# OsciloscopioVers_oFinal.net
KiCad netlist of a schematic drawn in EAGLE
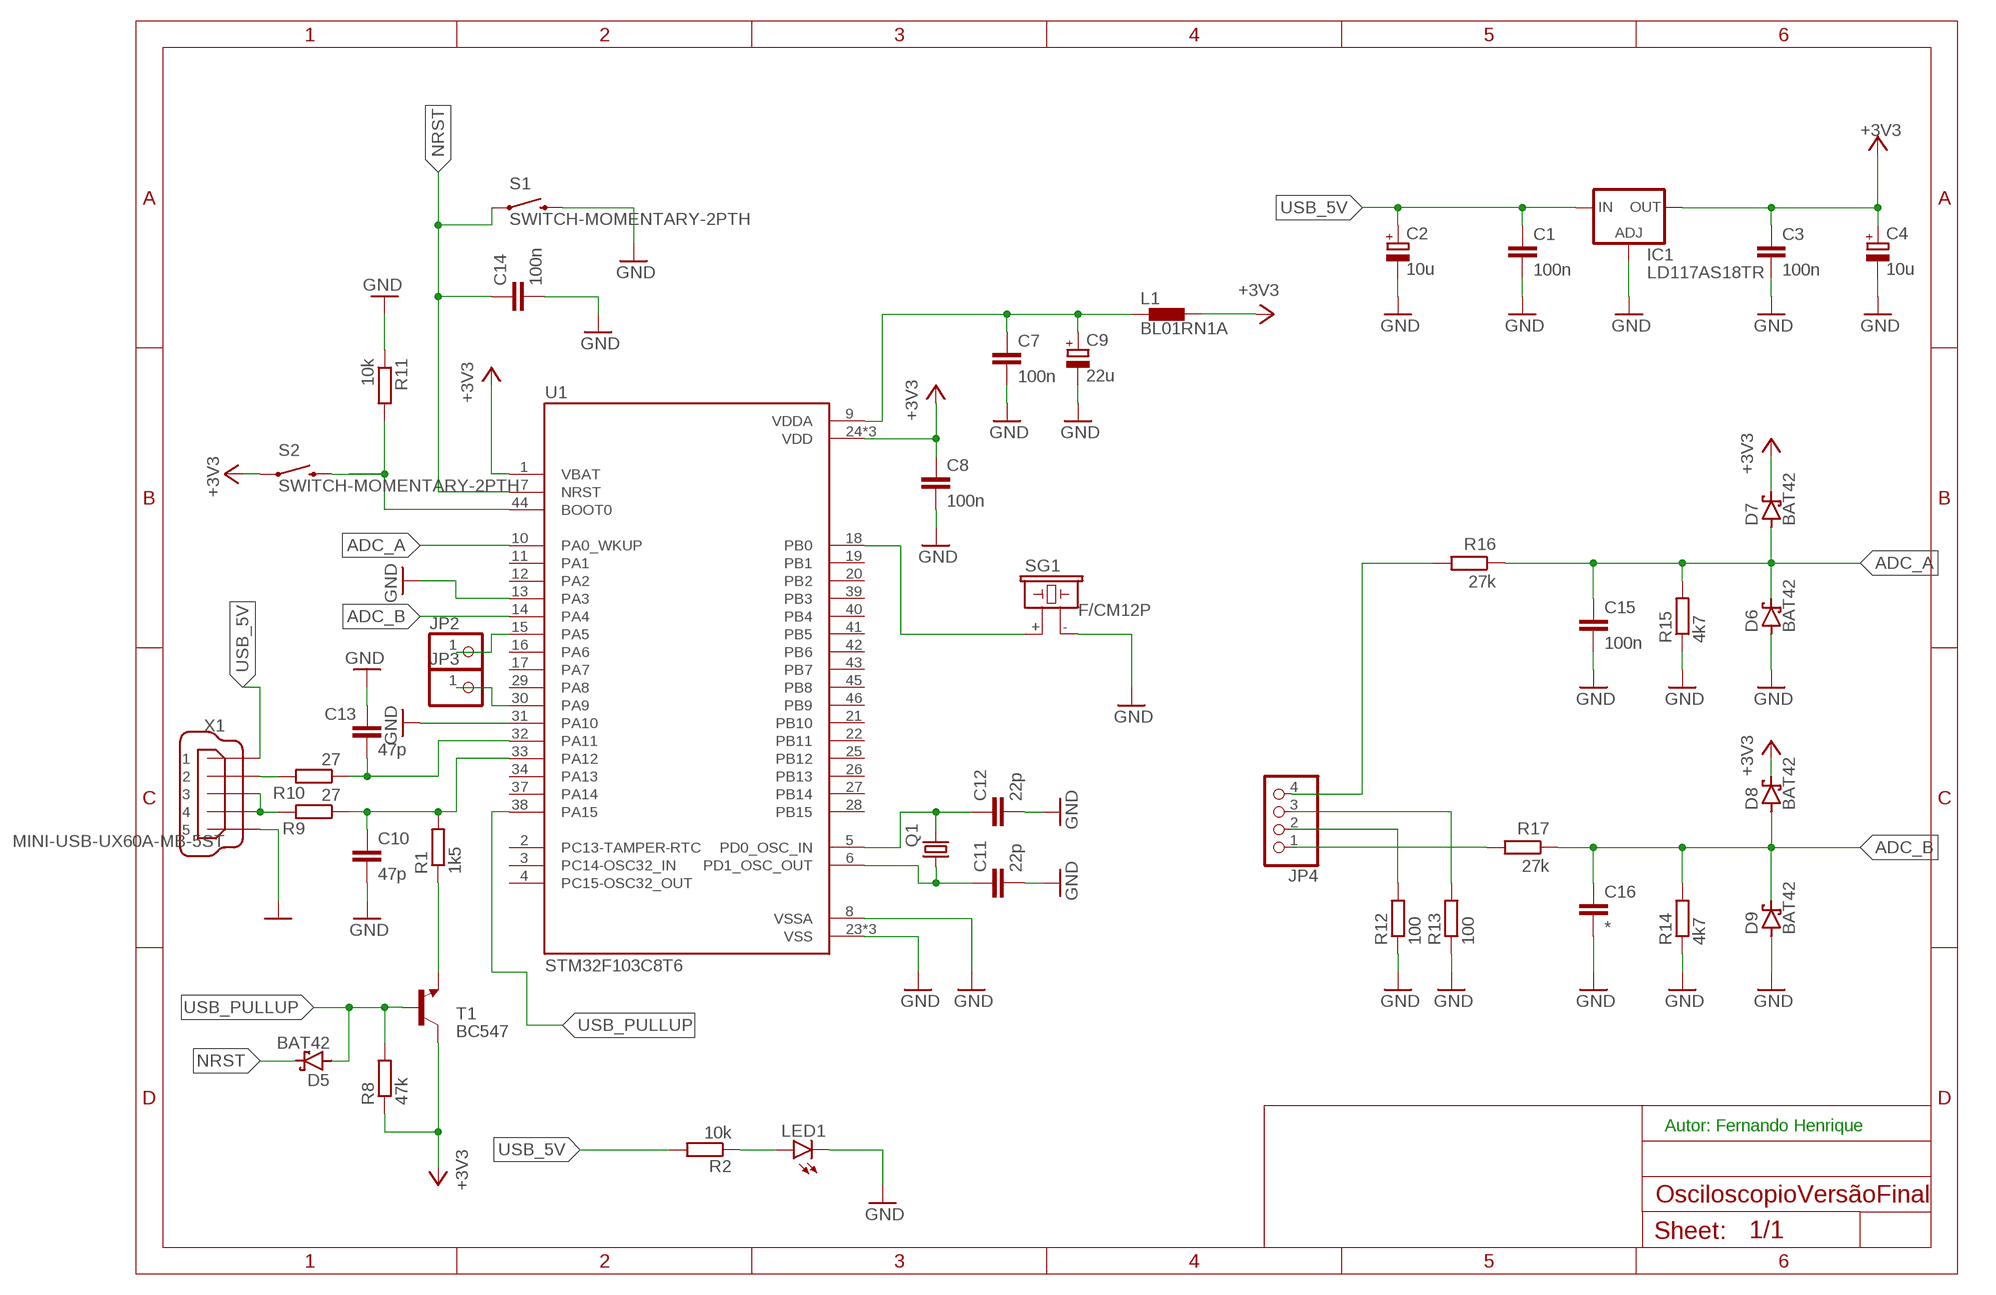
[diagram p0: schematic, sheet 1]

(export (version "E")
  (design (tool "Eeschema 10.0.6"))
  (components
    (comp (ref "C1")
      (value "100n")
      (footprint "eagle-import:C1206")
      (libsource (lib "eagle-import") (part "C-EUC1206"))
    )
    (comp (ref "C2")
      (value "10u")
      (footprint "eagle-import:B45181B")
      (libsource (lib "eagle-import") (part "CPOL-EUB45181B"))
    )
    (comp (ref "C3")
      (value "100n")
      (footprint "eagle-import:C1206")
      (libsource (lib "eagle-import") (part "C-EUC1206"))
    )
    (comp (ref "C4")
      (value "10u")
      (footprint "eagle-import:B45181B")
      (libsource (lib "eagle-import") (part "CPOL-EUB45181B"))
    )
    (comp (ref "C7")
      (value "100n")
      (footprint "eagle-import:C1206")
      (libsource (lib "eagle-import") (part "C-EUC1206"))
    )
    (comp (ref "C8")
      (value "100n")
      (footprint "eagle-import:C1206")
      (libsource (lib "eagle-import") (part "C-EUC1206"))
    )
    (comp (ref "C9")
      (value "22u")
      (footprint "eagle-import:B45181B")
      (libsource (lib "eagle-import") (part "CPOL-EUB45181B"))
    )
    (comp (ref "C10")
      (value "47p")
      (footprint "eagle-import:C1206")
      (libsource (lib "eagle-import") (part "C-EUC1206"))
    )
    (comp (ref "C11")
      (value "22p")
      (footprint "eagle-import:C1206")
      (libsource (lib "eagle-import") (part "C-EUC1206"))
    )
    (comp (ref "C12")
      (value "22p")
      (footprint "eagle-import:C1206")
      (libsource (lib "eagle-import") (part "C-EUC1206"))
    )
    (comp (ref "C13")
      (value "47p")
      (footprint "eagle-import:C1206")
      (libsource (lib "eagle-import") (part "C-EUC1206"))
    )
    (comp (ref "C14")
      (value "100n")
      (footprint "eagle-import:C1206")
      (libsource (lib "eagle-import") (part "C-EUC1206"))
    )
    (comp (ref "C15")
      (value "100n")
      (footprint "eagle-import:C1206")
      (libsource (lib "eagle-import") (part "C-EUC1206"))
    )
    (comp (ref "C16")
      (value "*")
      (footprint "eagle-import:C1206")
      (libsource (lib "eagle-import") (part "C-EUC1206"))
    )
    (comp (ref "D5")
      (value "BAT42")
      (footprint "eagle-import:DO35-10")
      (libsource (lib "eagle-import") (part "BAT42"))
    )
    (comp (ref "D6")
      (value "BAT42")
      (footprint "eagle-import:DO35-10")
      (libsource (lib "eagle-import") (part "BAT42"))
    )
    (comp (ref "D7")
      (value "BAT42")
      (footprint "eagle-import:DO35-10")
      (libsource (lib "eagle-import") (part "BAT42"))
    )
    (comp (ref "D8")
      (value "BAT42")
      (footprint "eagle-import:DO35-10")
      (libsource (lib "eagle-import") (part "BAT42"))
    )
    (comp (ref "D9")
      (value "BAT42")
      (footprint "eagle-import:DO35-10")
      (libsource (lib "eagle-import") (part "BAT42"))
    )
    (comp (ref "IC1")
      (value "LD117AS18TR")
      (footprint "eagle-import:SOT223")
      (libsource (lib "eagle-import") (part "LD117A?S18TR"))
    )
    (comp (ref "JP2")
      (value "PINHD-1X1")
      (footprint "eagle-import:1X01")
      (libsource (lib "eagle-import") (part "PINHD-1X1"))
    )
    (comp (ref "JP3")
      (value "PINHD-1X1")
      (footprint "eagle-import:1X01")
      (libsource (lib "eagle-import") (part "PINHD-1X1"))
    )
    (comp (ref "JP4")
      (value "PINHD-1X4")
      (footprint "eagle-import:1X04")
      (libsource (lib "eagle-import") (part "PINHD-1X4"))
    )
    (comp (ref "L1")
      (value "BL01RN1A")
      (footprint "eagle-import:BL01RN1A")
      (libsource (lib "eagle-import") (part "BL01RN1A"))
    )
    (comp (ref "LED1")
      (value "LED3MM")
      (footprint "eagle-import:LED3MM")
      (libsource (lib "eagle-import") (part "LED3MM"))
    )
    (comp (ref "Q1")
      (value "CRYSTALHC49U-V")
      (footprint "eagle-import:HC49U-V")
      (libsource (lib "eagle-import") (part "CRYSTALHC49U-V"))
    )
    (comp (ref "R1")
      (value "1k5")
      (footprint "eagle-import:R1206")
      (libsource (lib "eagle-import") (part "R-EU_R1206"))
    )
    (comp (ref "R2")
      (value "10k")
      (footprint "eagle-import:R1206")
      (libsource (lib "eagle-import") (part "R-EU_R1206"))
    )
    (comp (ref "R8")
      (value "47k")
      (footprint "eagle-import:R1206")
      (libsource (lib "eagle-import") (part "R-EU_R1206"))
    )
    (comp (ref "R9")
      (value "27")
      (footprint "eagle-import:R1206")
      (libsource (lib "eagle-import") (part "R-EU_R1206"))
    )
    (comp (ref "R10")
      (value "27")
      (footprint "eagle-import:R1206")
      (libsource (lib "eagle-import") (part "R-EU_R1206"))
    )
    (comp (ref "R11")
      (value "10k")
      (footprint "eagle-import:R1206")
      (libsource (lib "eagle-import") (part "R-EU_R1206"))
    )
    (comp (ref "R12")
      (value "100")
      (footprint "eagle-import:R1206")
      (libsource (lib "eagle-import") (part "R-EU_R1206"))
    )
    (comp (ref "R13")
      (value "100")
      (footprint "eagle-import:R1206")
      (libsource (lib "eagle-import") (part "R-EU_R1206"))
    )
    (comp (ref "R14")
      (value "4k7")
      (footprint "eagle-import:R1206")
      (libsource (lib "eagle-import") (part "R-EU_R1206"))
    )
    (comp (ref "R15")
      (value "4k7")
      (footprint "eagle-import:R1206")
      (libsource (lib "eagle-import") (part "R-EU_R1206"))
    )
    (comp (ref "R16")
      (value "27k")
      (footprint "eagle-import:R1206")
      (libsource (lib "eagle-import") (part "R-EU_R1206"))
    )
    (comp (ref "R17")
      (value "27k")
      (footprint "eagle-import:R1206")
      (libsource (lib "eagle-import") (part "R-EU_R1206"))
    )
    (comp (ref "S1")
      (value "SWITCH-MOMENTARY-2PTH")
      (footprint "eagle-import:TACTILE-PTH")
      (libsource (lib "eagle-import") (part "SWITCH-MOMENTARY-2PTH"))
    )
    (comp (ref "S2")
      (value "SWITCH-MOMENTARY-2PTH")
      (footprint "eagle-import:TACTILE-PTH")
      (libsource (lib "eagle-import") (part "SWITCH-MOMENTARY-2PTH"))
    )
    (comp (ref "SG1")
      (value "F/CM12P")
      (footprint "eagle-import:F_CM12P")
      (libsource (lib "eagle-import") (part "F/CM12P"))
    )
    (comp (ref "T1")
      (value "BC547")
      (footprint "eagle-import:TO92")
      (libsource (lib "eagle-import") (part "BC547"))
    )
    (comp (ref "U1")
      (value "STM32F103C8T6")
      (footprint "eagle-import:QFP50P900X900X160-48N")
      (fields (field (name "DIGI-KEY_PART_NUMBER") "497-6063-ND") (field (name "MF") "STMicroelectronics"))
      (libsource (lib "eagle-import") (part "STM32F103C8T6"))
    )
    (comp (ref "X1")
      (value "MINI-USB-UX60A-MB-5ST")
      (footprint "eagle-import:UX60A-MB-5ST")
      (libsource (lib "eagle-import") (part "MINI-USB-UX60A-MB-5ST"))
    )
  )
  (nets
    (net (code "1") (name "+3V3") (class "Default")
      (node (ref "C3") (pin "1") (pinfunction "1_1") (pintype "passive"))
      (node (ref "C4") (pin "+") (pinfunction "+_+") (pintype "passive"))
      (node (ref "C8") (pin "1") (pinfunction "1_1") (pintype "passive"))
      (node (ref "D7") (pin "C") (pinfunction "C_C") (pintype "passive"))
      (node (ref "D8") (pin "C") (pinfunction "C_C") (pintype "passive"))
      (node (ref "IC1") (pin "4") (pinfunction "OUT_4") (pintype "passive"))
      (node (ref "L1") (pin "2") (pinfunction "2_2") (pintype "passive"))
      (node (ref "R8") (pin "1") (pinfunction "1_1") (pintype "passive"))
      (node (ref "S2") (pin "1") (pinfunction "1_1") (pintype "passive"))
      (node (ref "T1") (pin "3") (pinfunction "C_3") (pintype "passive"))
      (node (ref "U1") (pin "1") (pinfunction "VBAT_1") (pintype "bidirectional"))
      (node (ref "U1") (pin "24") (pinfunction "VDD_24") (pintype "power_in"))
      (node (ref "U1") (pin "36") (pinfunction "VDD_36") (pintype "power_in"))
      (node (ref "U1") (pin "48") (pinfunction "VDD_48") (pintype "power_in"))
    )
    (net (code "2") (name "ADC_A") (class "Default")
      (node (ref "C15") (pin "1") (pinfunction "1_1") (pintype "passive"))
      (node (ref "D6") (pin "C") (pinfunction "C_C") (pintype "passive"))
      (node (ref "D7") (pin "A") (pinfunction "A_A") (pintype "passive"))
      (node (ref "R15") (pin "2") (pinfunction "2_2") (pintype "passive"))
      (node (ref "R16") (pin "1") (pinfunction "1_1") (pintype "passive"))
      (node (ref "U1") (pin "10") (pinfunction "PA0_WKUP_10") (pintype "bidirectional"))
    )
    (net (code "3") (name "ADC_B") (class "Default")
      (node (ref "C16") (pin "1") (pinfunction "1_1") (pintype "passive"))
      (node (ref "D8") (pin "A") (pinfunction "A_A") (pintype "passive"))
      (node (ref "D9") (pin "C") (pinfunction "C_C") (pintype "passive"))
      (node (ref "R14") (pin "2") (pinfunction "2_2") (pintype "passive"))
      (node (ref "R17") (pin "1") (pinfunction "1_1") (pintype "passive"))
      (node (ref "U1") (pin "14") (pinfunction "PA4_14") (pintype "bidirectional"))
    )
    (net (code "4") (name "GND") (class "Default")
      (node (ref "C1") (pin "2") (pinfunction "2_2") (pintype "passive"))
      (node (ref "C10") (pin "2") (pinfunction "2_2") (pintype "passive"))
      (node (ref "C11") (pin "2") (pinfunction "2_2") (pintype "passive"))
      (node (ref "C12") (pin "2") (pinfunction "2_2") (pintype "passive"))
      (node (ref "C13") (pin "1") (pinfunction "1_1") (pintype "passive"))
      (node (ref "C14") (pin "2") (pinfunction "2_2") (pintype "passive"))
      (node (ref "C15") (pin "2") (pinfunction "2_2") (pintype "passive"))
      (node (ref "C16") (pin "2") (pinfunction "2_2") (pintype "passive"))
      (node (ref "C2") (pin "-") (pinfunction "-_-") (pintype "passive"))
      (node (ref "C3") (pin "2") (pinfunction "2_2") (pintype "passive"))
      (node (ref "C4") (pin "-") (pinfunction "-_-") (pintype "passive"))
      (node (ref "C7") (pin "2") (pinfunction "2_2") (pintype "passive"))
      (node (ref "C8") (pin "2") (pinfunction "2_2") (pintype "passive"))
      (node (ref "C9") (pin "-") (pinfunction "-_-") (pintype "passive"))
      (node (ref "D6") (pin "A") (pinfunction "A_A") (pintype "passive"))
      (node (ref "D9") (pin "A") (pinfunction "A_A") (pintype "passive"))
      (node (ref "IC1") (pin "1") (pinfunction "ADJ_1") (pintype "input"))
      (node (ref "LED1") (pin "K") (pinfunction "C_K") (pintype "passive"))
      (node (ref "R11") (pin "1") (pinfunction "1_1") (pintype "passive"))
      (node (ref "R12") (pin "1") (pinfunction "1_1") (pintype "passive"))
      (node (ref "R13") (pin "1") (pinfunction "1_1") (pintype "passive"))
      (node (ref "R14") (pin "1") (pinfunction "1_1") (pintype "passive"))
      (node (ref "R15") (pin "1") (pinfunction "1_1") (pintype "passive"))
      (node (ref "S1") (pin "3") (pinfunction "2_3") (pintype "passive"))
      (node (ref "SG1") (pin "-") (pinfunction "2_-") (pintype "passive"))
      (node (ref "U1") (pin "13") (pinfunction "PA3_13") (pintype "bidirectional"))
      (node (ref "U1") (pin "23") (pinfunction "VSS_23") (pintype "power_in"))
      (node (ref "U1") (pin "31") (pinfunction "PA10_31") (pintype "bidirectional"))
      (node (ref "U1") (pin "35") (pinfunction "VSS_35") (pintype "power_in"))
      (node (ref "U1") (pin "47") (pinfunction "VSS_47") (pintype "power_in"))
      (node (ref "U1") (pin "8") (pinfunction "VSSA_8") (pintype "power_in"))
      (node (ref "X1") (pin "5") (pinfunction "5_5") (pintype "input"))
    )
    (net (code "5") (name "NRST") (class "Default")
      (node (ref "C14") (pin "1") (pinfunction "1_1") (pintype "passive"))
      (node (ref "D5") (pin "C") (pinfunction "C_C") (pintype "passive"))
      (node (ref "S1") (pin "1") (pinfunction "1_1") (pintype "passive"))
      (node (ref "U1") (pin "7") (pinfunction "NRST_7") (pintype "input"))
    )
    (net (code "6") (name "Net-(JP4-Pad1)") (class "Default")
      (node (ref "JP4") (pin "1") (pinfunction "1_1") (pintype "passive"))
      (node (ref "R17") (pin "2") (pinfunction "2_2") (pintype "passive"))
    )
    (net (code "7") (name "Net-(JP4-Pad2)") (class "Default")
      (node (ref "JP4") (pin "2") (pinfunction "2_2") (pintype "passive"))
      (node (ref "R12") (pin "2") (pinfunction "2_2") (pintype "passive"))
    )
    (net (code "8") (name "Net-(JP4-Pad3)") (class "Default")
      (node (ref "JP4") (pin "3") (pinfunction "3_3") (pintype "passive"))
      (node (ref "R13") (pin "2") (pinfunction "2_2") (pintype "passive"))
    )
    (net (code "9") (name "Net-(JP4-Pad4)") (class "Default")
      (node (ref "JP4") (pin "4") (pinfunction "4_4") (pintype "passive"))
      (node (ref "R16") (pin "2") (pinfunction "2_2") (pintype "passive"))
    )
    (net (code "10") (name "Net-(LED1-PadA)") (class "Default")
      (node (ref "LED1") (pin "A") (pinfunction "A_A") (pintype "passive"))
      (node (ref "R2") (pin "1") (pinfunction "1_1") (pintype "passive"))
    )
    (net (code "11") (name "Net-(R9-Pad2)") (class "Default")
      (node (ref "R9") (pin "2") (pinfunction "2_2") (pintype "passive"))
      (node (ref "X1") (pin "3") (pinfunction "3_3") (pintype "input"))
      (node (ref "X1") (pin "4") (pinfunction "4_4") (pintype "input"))
    )
    (net (code "12") (name "Net-(R10-Pad2)") (class "Default")
      (node (ref "R10") (pin "2") (pinfunction "2_2") (pintype "passive"))
      (node (ref "X1") (pin "2") (pinfunction "2_2") (pintype "input"))
    )
    (net (code "13") (name "Net-(S2-2)") (class "Default")
      (node (ref "R11") (pin "2") (pinfunction "2_2") (pintype "passive"))
      (node (ref "S2") (pin "3") (pinfunction "2_3") (pintype "passive"))
      (node (ref "U1") (pin "44") (pinfunction "BOOT0_44") (pintype "input"))
    )
    (net (code "14") (name "Net-(SG1-1)") (class "Default")
      (node (ref "SG1") (pin "+") (pinfunction "1_+") (pintype "passive"))
      (node (ref "U1") (pin "18") (pinfunction "PB0_18") (pintype "bidirectional"))
    )
    (net (code "15") (name "Net-(T1-E)") (class "Default")
      (node (ref "R1") (pin "1") (pinfunction "1_1") (pintype "passive"))
      (node (ref "T1") (pin "1") (pinfunction "E_1") (pintype "passive"))
    )
    (net (code "16") (name "Net-(U1-PA5)") (class "Default")
      (node (ref "JP2") (pin "1") (pinfunction "1_1") (pintype "passive"))
      (node (ref "U1") (pin "15") (pinfunction "PA5_15") (pintype "bidirectional"))
    )
    (net (code "17") (name "Net-(U1-PA9)") (class "Default")
      (node (ref "JP3") (pin "1") (pinfunction "1_1") (pintype "passive"))
      (node (ref "U1") (pin "30") (pinfunction "PA9_30") (pintype "bidirectional"))
    )
    (net (code "18") (name "Net-(U1-PA11)") (class "Default")
      (node (ref "C13") (pin "2") (pinfunction "2_2") (pintype "passive"))
      (node (ref "R10") (pin "1") (pinfunction "1_1") (pintype "passive"))
      (node (ref "U1") (pin "32") (pinfunction "PA11_32") (pintype "bidirectional"))
    )
    (net (code "19") (name "Net-(U1-PA12)") (class "Default")
      (node (ref "C10") (pin "1") (pinfunction "1_1") (pintype "passive"))
      (node (ref "R1") (pin "2") (pinfunction "2_2") (pintype "passive"))
      (node (ref "R9") (pin "1") (pinfunction "1_1") (pintype "passive"))
      (node (ref "U1") (pin "33") (pinfunction "PA12_33") (pintype "bidirectional"))
    )
    (net (code "20") (name "Net-(U1-PD0_OSC_IN)") (class "Default")
      (node (ref "C12") (pin "1") (pinfunction "1_1") (pintype "passive"))
      (node (ref "Q1") (pin "2") (pinfunction "2_2") (pintype "passive"))
      (node (ref "U1") (pin "5") (pinfunction "PD0_OSC_IN_5") (pintype "bidirectional"))
    )
    (net (code "21") (name "Net-(U1-PD1_OSC_OUT)") (class "Default")
      (node (ref "C11") (pin "1") (pinfunction "1_1") (pintype "passive"))
      (node (ref "Q1") (pin "1") (pinfunction "1_1") (pintype "passive"))
      (node (ref "U1") (pin "6") (pinfunction "PD1_OSC_OUT_6") (pintype "bidirectional"))
    )
    (net (code "22") (name "Net-(U1-VDDA)") (class "Default")
      (node (ref "C7") (pin "1") (pinfunction "1_1") (pintype "passive"))
      (node (ref "C9") (pin "+") (pinfunction "+_+") (pintype "passive"))
      (node (ref "L1") (pin "1") (pinfunction "1_1") (pintype "passive"))
      (node (ref "U1") (pin "9") (pinfunction "VDDA_9") (pintype "power_in"))
    )
    (net (code "23") (name "USB_5V") (class "Default")
      (node (ref "C1") (pin "1") (pinfunction "1_1") (pintype "passive"))
      (node (ref "C2") (pin "+") (pinfunction "+_+") (pintype "passive"))
      (node (ref "IC1") (pin "3") (pinfunction "IN_3") (pintype "input"))
      (node (ref "R2") (pin "2") (pinfunction "2_2") (pintype "passive"))
      (node (ref "X1") (pin "1") (pinfunction "1_1") (pintype "input"))
    )
    (net (code "24") (name "USB_PULLUP") (class "Default")
      (node (ref "D5") (pin "A") (pinfunction "A_A") (pintype "passive"))
      (node (ref "R8") (pin "2") (pinfunction "2_2") (pintype "passive"))
      (node (ref "T1") (pin "2") (pinfunction "B_2") (pintype "passive"))
      (node (ref "U1") (pin "38") (pinfunction "PA15_38") (pintype "bidirectional"))
    )
    (net (code "25") (name "unconnected-(U1-PA1-Pad11)") (class "Default")
      (node (ref "U1") (pin "11") (pinfunction "PA1_11") (pintype "bidirectional"))
    )
    (net (code "26") (name "unconnected-(U1-PA2-Pad12)") (class "Default")
      (node (ref "U1") (pin "12") (pinfunction "PA2_12") (pintype "bidirectional"))
    )
    (net (code "27") (name "unconnected-(U1-PA6-Pad16)") (class "Default")
      (node (ref "U1") (pin "16") (pinfunction "PA6_16") (pintype "bidirectional"))
    )
    (net (code "28") (name "unconnected-(U1-PA7-Pad17)") (class "Default")
      (node (ref "U1") (pin "17") (pinfunction "PA7_17") (pintype "bidirectional"))
    )
    (net (code "29") (name "unconnected-(U1-PA8-Pad29)") (class "Default")
      (node (ref "U1") (pin "29") (pinfunction "PA8_29") (pintype "bidirectional"))
    )
    (net (code "30") (name "unconnected-(U1-PA13-Pad34)") (class "Default")
      (node (ref "U1") (pin "34") (pinfunction "PA13_34") (pintype "bidirectional"))
    )
    (net (code "31") (name "unconnected-(U1-PA14-Pad37)") (class "Default")
      (node (ref "U1") (pin "37") (pinfunction "PA14_37") (pintype "bidirectional"))
    )
    (net (code "32") (name "unconnected-(U1-PB1-Pad19)") (class "Default")
      (node (ref "U1") (pin "19") (pinfunction "PB1_19") (pintype "bidirectional"))
    )
    (net (code "33") (name "unconnected-(U1-PB2-Pad20)") (class "Default")
      (node (ref "U1") (pin "20") (pinfunction "PB2_20") (pintype "bidirectional"))
    )
    (net (code "34") (name "unconnected-(U1-PB3-Pad39)") (class "Default")
      (node (ref "U1") (pin "39") (pinfunction "PB3_39") (pintype "bidirectional"))
    )
    (net (code "35") (name "unconnected-(U1-PB4-Pad40)") (class "Default")
      (node (ref "U1") (pin "40") (pinfunction "PB4_40") (pintype "bidirectional"))
    )
    (net (code "36") (name "unconnected-(U1-PB5-Pad41)") (class "Default")
      (node (ref "U1") (pin "41") (pinfunction "PB5_41") (pintype "bidirectional"))
    )
    (net (code "37") (name "unconnected-(U1-PB6-Pad42)") (class "Default")
      (node (ref "U1") (pin "42") (pinfunction "PB6_42") (pintype "bidirectional"))
    )
    (net (code "38") (name "unconnected-(U1-PB7-Pad43)") (class "Default")
      (node (ref "U1") (pin "43") (pinfunction "PB7_43") (pintype "bidirectional"))
    )
    (net (code "39") (name "unconnected-(U1-PB8-Pad45)") (class "Default")
      (node (ref "U1") (pin "45") (pinfunction "PB8_45") (pintype "bidirectional"))
    )
    (net (code "40") (name "unconnected-(U1-PB9-Pad46)") (class "Default")
      (node (ref "U1") (pin "46") (pinfunction "PB9_46") (pintype "bidirectional"))
    )
    (net (code "41") (name "unconnected-(U1-PB10-Pad21)") (class "Default")
      (node (ref "U1") (pin "21") (pinfunction "PB10_21") (pintype "bidirectional"))
    )
    (net (code "42") (name "unconnected-(U1-PB11-Pad22)") (class "Default")
      (node (ref "U1") (pin "22") (pinfunction "PB11_22") (pintype "bidirectional"))
    )
    (net (code "43") (name "unconnected-(U1-PB12-Pad25)") (class "Default")
      (node (ref "U1") (pin "25") (pinfunction "PB12_25") (pintype "bidirectional"))
    )
    (net (code "44") (name "unconnected-(U1-PB13-Pad26)") (class "Default")
      (node (ref "U1") (pin "26") (pinfunction "PB13_26") (pintype "bidirectional"))
    )
    (net (code "45") (name "unconnected-(U1-PB14-Pad27)") (class "Default")
      (node (ref "U1") (pin "27") (pinfunction "PB14_27") (pintype "bidirectional"))
    )
    (net (code "46") (name "unconnected-(U1-PB15-Pad28)") (class "Default")
      (node (ref "U1") (pin "28") (pinfunction "PB15_28") (pintype "bidirectional"))
    )
    (net (code "47") (name "unconnected-(U1-PC13-TAMPER-RTC-Pad2)") (class "Default")
      (node (ref "U1") (pin "2") (pinfunction "PC13-TAMPER-RTC_2") (pintype "bidirectional"))
    )
    (net (code "48") (name "unconnected-(U1-PC14-OSC32_IN-Pad3)") (class "Default")
      (node (ref "U1") (pin "3") (pinfunction "PC14-OSC32_IN_3") (pintype "bidirectional"))
    )
    (net (code "49") (name "unconnected-(U1-PC15-OSC32_OUT-Pad4)") (class "Default")
      (node (ref "U1") (pin "4") (pinfunction "PC15-OSC32_OUT_4") (pintype "bidirectional"))
    )
  )
)
